# Power_Monitoring_TPS3803.net
KiCad netlist of a schematic drawn in Altium Designer
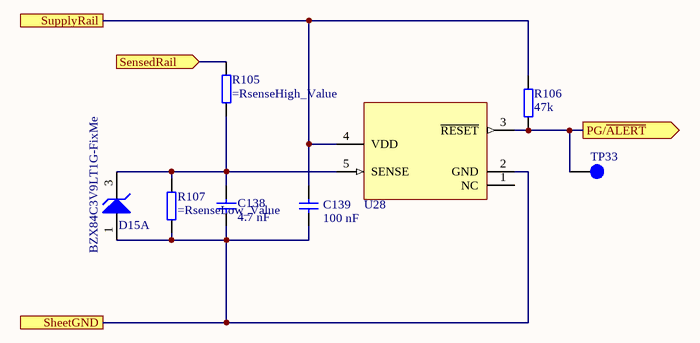
[diagram p0: Power_Monitoring_TPS3803.SchDoc]

(export (version "E")
  (design (tool "Eeschema 10.0.6"))
  (components
    (comp (ref "C138")
      (value "4.7 nF")
      (footprint "C_0603_TE")
      (description "50V 4.7nF C0G ±5% 0603 Multilayer Ceramic Capacitors MLCC")
      (fields
        (field (name "TOLERANCE") "5%")
        (field (name "MANUFACTURER PART NUMBER") "GRM1885C1H472JA01D")
        (field (name "CREATED FROM") "MGeier")
      )
      (libsource (lib "user") (part "CAP-NP"))
    )
    (comp (ref "C139")
      (value "100 nF")
      (footprint "C_0603_TE")
      (description "Generic capacitor")
      (fields
        (field (name "MANUFACTURER PART NUMBER") "UZgen_C_0603_100nF_50V_X7R")
        (field (name "MANUFACTURER") "UZgen")
        (field (name "CREATED FROM") "AGeiger")
      )
      (libsource (lib "user") (part "CAP-NP"))
    )
    (comp (ref "D15")
      (value "BZX84C3V9LT1G-FixMe")
      (footprint "SOT-23-3_ONSC")
      (description "Zener Diode, 3.9 V, 0.25 W, 5 %")
      (fields
        (field (name "MANUFACTURER") "onsemi")
        (field (name "LCSC PART NUMBER") "C94414")
        (field (name "CREATED FROM") "FRosner")
      )
      (libsource (lib "user") (part "Zener_Diode_BZX84CxxxLT1G"))
    )
    (comp (ref "R105")
      (value "~")
      (footprint "R_0603_TE")
      (description "Generic resistor (parametric)")
      (fields
        (field (name "MANUFACTURER") "UZgen")
        (field (name "TOLERANCE") "1 %")
        (field (name "CREATED FROM") "UZgenTool")
      )
      (libsource (lib "user") (part "RES"))
    )
    (comp (ref "R106")
      (value "47k")
      (footprint "R_0603_TE")
      (description "Generic resistor")
      (fields
        (field (name "MANUFACTURER PART NUMBER") "UZgen_R_0603_47k")
        (field (name "MANUFACTURER") "UZgen")
        (field (name "CREATED FROM") "UZgenTool")
      )
      (libsource (lib "user") (part "RES"))
    )
    (comp (ref "R107")
      (value "~")
      (footprint "R_0603_TE")
      (description "Generic resistor (parametric)")
      (fields
        (field (name "MANUFACTURER") "UZgen")
        (field (name "TOLERANCE") "1 %")
        (field (name "CREATED FROM") "UZgenTool")
      )
      (libsource (lib "user") (part "RES"))
    )
    (comp (ref "TP33")
      (value "Testpoint 1mm")
      (footprint "TP_1mm")
      (fields
        (field (name "MANUFACTURER PART NUMBER") "NULL")
        (field (name "CREATED") "2018_06_25_AGeiger")
        (field (name "CREATED FROM") "AGeiger")
      )
      (libsource (lib "user") (part "TP_1mm"))
    )
    (comp (ref "U28")
      (value "TPS3803-01QDCKRQ1")
      (footprint "FP-DCK0005A-IPC_B")
      (description "Supervisory Circuits Auto Cat Dual Vltg Detectors")
      (fields
        (field (name "MANUFACTURER") "Texas Instruments")
        (field (name "LCSC PART NUMBER") "C129371")
        (field (name "CREATED FROM") "FRosner")
      )
      (libsource (lib "user") (part "TPS3803"))
    )
  )
  (nets
    (net (code "1") (name "/PG{slash}~{ALERT}") (class "Default")
      (node (ref "R106") (pin "1") (pinfunction "1_1") (pintype "passive"))
      (node (ref "TP33") (pin "1") (pintype "passive"))
      (node (ref "U28") (pin "3") (pinfunction "~{RESET}_3") (pintype "output"))
    )
    (net (code "2") (name "/SensedRail") (class "Default")
      (node (ref "R105") (pin "2") (pinfunction "2_2") (pintype "passive"))
    )
    (net (code "3") (name "/SheetGND") (class "Default")
      (node (ref "C138") (pin "2") (pinfunction "2_2") (pintype "passive"))
      (node (ref "C139") (pin "1") (pinfunction "1_1") (pintype "passive"))
      (node (ref "D15") (pin "1") (pinfunction "A_1") (pintype "passive"))
      (node (ref "R107") (pin "1") (pinfunction "1_1") (pintype "passive"))
      (node (ref "U28") (pin "2") (pinfunction "GND_2") (pintype "passive"))
    )
    (net (code "4") (name "/SupplyRail") (class "Default")
      (node (ref "C139") (pin "2") (pinfunction "2_2") (pintype "passive"))
      (node (ref "R106") (pin "2") (pinfunction "2_2") (pintype "passive"))
      (node (ref "U28") (pin "4") (pinfunction "VDD_4") (pintype "power_in"))
    )
    (net (code "5") (name "Net-(D15A-K)") (class "Default")
      (node (ref "C138") (pin "1") (pinfunction "1_1") (pintype "passive"))
      (node (ref "D15") (pin "3") (pinfunction "K_3") (pintype "passive"))
      (node (ref "R105") (pin "1") (pinfunction "1_1") (pintype "passive"))
      (node (ref "R107") (pin "2") (pinfunction "2_2") (pintype "passive"))
      (node (ref "U28") (pin "5") (pinfunction "SENSE_5") (pintype "input"))
    )
    (net (code "6") (name "unconnected-(U28-NC-Pad1)") (class "Default")
      (node (ref "U28") (pin "1") (pinfunction "NC_1") (pintype "passive"))
    )
  )
)
